# Sheet1.net
KiCad netlist of a schematic drawn in Altium Designer
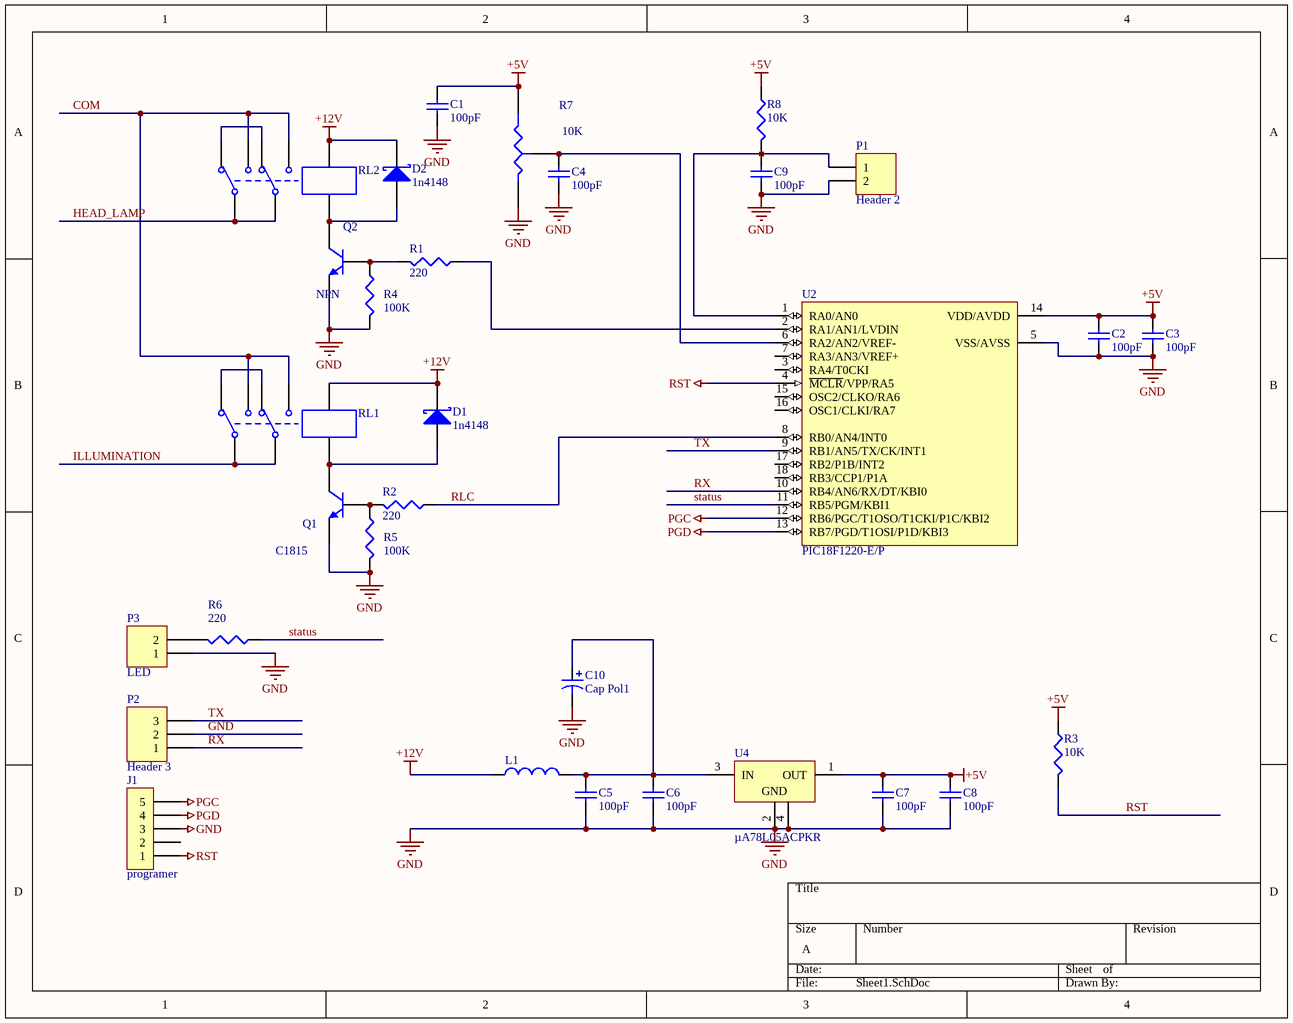
[diagram p0: Sheet1.SchDoc]

(export (version "E")
  (design (tool "Eeschema 10.0.6"))
  (components
    (comp (ref "C1")
      (value "100pF")
      (footprint "RESC2012L")
      (description "Capacitor (Semiconductor SIM Model)")
      (fields (field (name "Comment") "Cap Semi") (field (name "PUBLISHER") "Altium Limited"))
      (libsource (lib "Miscellaneous Devices") (part "Cap Semi"))
    )
    (comp (ref "C2")
      (value "100pF")
      (footprint "RESC2012L")
      (description "Capacitor (Semiconductor SIM Model)")
      (fields (field (name "Comment") "Cap Semi") (field (name "PUBLISHER") "Altium Limited"))
      (libsource (lib "Miscellaneous Devices") (part "Cap Semi"))
    )
    (comp (ref "C3")
      (value "100pF")
      (footprint "RESC2012L")
      (description "Capacitor (Semiconductor SIM Model)")
      (fields (field (name "Comment") "Cap Semi") (field (name "PUBLISHER") "Altium Limited"))
      (libsource (lib "Miscellaneous Devices") (part "Cap Semi"))
    )
    (comp (ref "C4")
      (value "100pF")
      (footprint "RESC2012L")
      (description "Capacitor (Semiconductor SIM Model)")
      (fields (field (name "Comment") "Cap Semi") (field (name "PUBLISHER") "Altium Limited"))
      (libsource (lib "Miscellaneous Devices") (part "Cap Semi"))
    )
    (comp (ref "C5")
      (value "100pF")
      (footprint "RESC2012L")
      (description "Capacitor (Semiconductor SIM Model)")
      (fields (field (name "Comment") "Cap Semi") (field (name "PUBLISHER") "Altium Limited"))
      (libsource (lib "Miscellaneous Devices") (part "Cap Semi"))
    )
    (comp (ref "C6")
      (value "100pF")
      (footprint "RESC2012L")
      (description "Capacitor (Semiconductor SIM Model)")
      (fields (field (name "Comment") "Cap Semi") (field (name "PUBLISHER") "Altium Limited"))
      (libsource (lib "Miscellaneous Devices") (part "Cap Semi"))
    )
    (comp (ref "C7")
      (value "100pF")
      (footprint "RESC2012L")
      (description "Capacitor (Semiconductor SIM Model)")
      (fields (field (name "Comment") "Cap Semi") (field (name "PUBLISHER") "Altium Limited"))
      (libsource (lib "Miscellaneous Devices") (part "Cap Semi"))
    )
    (comp (ref "C8")
      (value "100pF")
      (footprint "RESC2012L")
      (description "Capacitor (Semiconductor SIM Model)")
      (fields (field (name "Comment") "Cap Semi") (field (name "PUBLISHER") "Altium Limited"))
      (libsource (lib "Miscellaneous Devices") (part "Cap Semi"))
    )
    (comp (ref "C9")
      (value "100pF")
      (footprint "RESC2012L")
      (description "Capacitor (Semiconductor SIM Model)")
      (fields (field (name "Comment") "Cap Semi") (field (name "PUBLISHER") "Altium Limited"))
      (libsource (lib "Miscellaneous Devices") (part "Cap Semi"))
    )
    (comp (ref "C10")
      (value "Cap Pol1")
      (footprint "CAP5")
      (description "Polarized Capacitor (Radial)")
      (fields (field (name "PUBLISHER") "Altium Limited"))
      (libsource (lib "Miscellaneous Devices") (part "Cap Pol1"))
    )
    (comp (ref "D1")
      (value "1n4148")
      (footprint "MELF-D5022-2009")
      (description "Schottky Diode")
      (fields (field (name "PUBLISHER") "Altium Limited"))
      (libsource (lib "Schlib1") (part "1N4148_SMD"))
    )
    (comp (ref "D2")
      (value "1n4148")
      (footprint "MELF-D5022-2009")
      (description "Schottky Diode")
      (fields (field (name "PUBLISHER") "Altium Limited"))
      (libsource (lib "Schlib1") (part "1N4148_SMD"))
    )
    (comp (ref "J1")
      (value "programer")
      (footprint "HDR1x5")
      (description "Connector")
      (libsource (lib "*") (part "CON5"))
    )
    (comp (ref "L1")
      (value "~")
      (footprint "INDC3216")
      (description "Inductor")
      (fields (field (name "PUBLISHER") "Altium Limited"))
      (libsource (lib "Miscellaneous Devices") (part "Inductor"))
    )
    (comp (ref "P1")
      (value "Header 2")
      (footprint "HDR1X2")
      (description "Header, 2-Pin")
      (fields (field (name "PUBLISHER") "Altium Limited"))
      (libsource (lib "Miscellaneous Connectors") (part "Header 2"))
    )
    (comp (ref "P2")
      (value "Header 3")
      (footprint "HDR1X3")
      (description "Header, 3-Pin")
      (fields (field (name "PUBLISHER") "Altium Limited"))
      (libsource (lib "Miscellaneous Connectors") (part "Header 3"))
    )
    (comp (ref "P3")
      (value "LED")
      (footprint "HDR1X2")
      (description "Header, 2-Pin")
      (fields (field (name "PUBLISHER") "Altium Limited"))
      (libsource (lib "") (part "Header 2_1"))
    )
    (comp (ref "Q1")
      (value "C1815")
      (footprint "SOT-23B")
      (description "NPN Bipolar Transistor")
      (fields (field (name "PUBLISHER") "Altium Limited"))
      (libsource (lib "Miscellaneous Devices") (part "NPN"))
    )
    (comp (ref "Q2")
      (value "NPN")
      (footprint "SOT-23B")
      (description "NPN Bipolar Transistor")
      (fields (field (name "PUBLISHER") "Altium Limited"))
      (libsource (lib "Miscellaneous Devices") (part "NPN"))
    )
    (comp (ref "R1")
      (value "220")
      (footprint "RESC2012L")
      (description "Resistor")
      (fields (field (name "Comment") "Res3") (field (name "PUBLISHER") "Altium Limited"))
      (libsource (lib "Miscellaneous Devices") (part "Res3"))
    )
    (comp (ref "R2")
      (value "220")
      (footprint "RESC2012L")
      (description "Resistor")
      (fields (field (name "Comment") "Res3") (field (name "PUBLISHER") "Altium Limited"))
      (libsource (lib "Miscellaneous Devices") (part "Res3"))
    )
    (comp (ref "R3")
      (value "10K")
      (footprint "RESC2012L")
      (description "Resistor")
      (fields (field (name "Comment") "Res3") (field (name "PUBLISHER") "Altium Limited"))
      (libsource (lib "Miscellaneous Devices") (part "Res3"))
    )
    (comp (ref "R4")
      (value "100K")
      (footprint "RESC2012L")
      (description "Resistor")
      (fields (field (name "Comment") "Res3") (field (name "PUBLISHER") "Altium Limited"))
      (libsource (lib "Miscellaneous Devices") (part "Res3"))
    )
    (comp (ref "R5")
      (value "100K")
      (footprint "RESC2012L")
      (description "Resistor")
      (fields (field (name "Comment") "Res3") (field (name "PUBLISHER") "Altium Limited"))
      (libsource (lib "Miscellaneous Devices") (part "Res3"))
    )
    (comp (ref "R6")
      (value "220")
      (footprint "RESC2012L")
      (description "Resistor")
      (fields (field (name "Comment") "Res3") (field (name "PUBLISHER") "Altium Limited"))
      (libsource (lib "Miscellaneous Devices") (part "Res3"))
    )
    (comp (ref "R7")
      (value "10K")
      (footprint "VR_V_MH")
      (description "Tapped Resistor")
      (fields (field (name "Comment") "Res Tap") (field (name "PUBLISHER") "Altium Limited"))
      (libsource (lib "Miscellaneous Devices") (part "Res Tap"))
    )
    (comp (ref "R8")
      (value "10K")
      (footprint "RESC2012L")
      (description "Resistor")
      (fields (field (name "Comment") "Res3") (field (name "PUBLISHER") "Altium Limited"))
      (libsource (lib "Miscellaneous Devices") (part "Res3"))
    )
    (comp (ref "RL1")
      (value "Relay-DPDT")
      (footprint "RELAY_8PIN_MH")
      (description "Dual-Pole Dual-Throw Relay")
      (fields (field (name "PUBLISHER") "Altium Limited"))
      (libsource (lib "Miscellaneous Devices") (part "Relay-DPDT"))
    )
    (comp (ref "RL2")
      (value "Relay-DPDT")
      (footprint "RELAY_8PIN_MH")
      (description "Dual-Pole Dual-Throw Relay")
      (fields (field (name "PUBLISHER") "Altium Limited"))
      (libsource (lib "Miscellaneous Devices") (part "Relay-DPDT"))
    )
    (comp (ref "U2")
      (value "PIC18F1220-E/P")
      (footprint "PDIP300-P18")
      (fields (field (name "PUBLISHER") "Altium Limited"))
      (libsource (lib "Microchip Microcontroller 8-Bit PIC18") (part "PIC18F1220-E/P"))
    )
    (comp (ref "U4")
      (value "µA78L05ACPKR")
      (footprint "PK03")
      (description "Positive-Voltage Regulator")
      (fields (field (name "PUBLISHER") "Altium Limited"))
      (libsource (lib "Schlib1") (part "µA78L05ACPKR"))
    )
  )
  (nets
    (net (code "1") (name "+5V") (class "Default")
      (node (ref "C1") (pin "2") (pinfunction "2_2") (pintype "passive"))
      (node (ref "C2") (pin "2") (pinfunction "2_2") (pintype "passive"))
      (node (ref "C3") (pin "2") (pinfunction "2_2") (pintype "passive"))
      (node (ref "C7") (pin "2") (pinfunction "2_2") (pintype "passive"))
      (node (ref "C8") (pin "2") (pinfunction "2_2") (pintype "passive"))
      (node (ref "R3") (pin "1") (pinfunction "1_1") (pintype "passive"))
      (node (ref "R7") (pin "2") (pinfunction "B_2") (pintype "passive"))
      (node (ref "R8") (pin "1") (pinfunction "1_1") (pintype "passive"))
      (node (ref "U2") (pin "14") (pinfunction "VDD/AVDD_14") (pintype "power_in"))
      (node (ref "U4") (pin "1") (pinfunction "OUT_1") (pintype "power_in"))
    )
    (net (code "2") (name "+12V") (class "Default")
      (node (ref "D1") (pin "2") (pinfunction "K_2") (pintype "passive"))
      (node (ref "D2") (pin "2") (pinfunction "K_2") (pintype "passive"))
      (node (ref "L1") (pin "1") (pinfunction "1_1") (pintype "passive"))
      (node (ref "RL1") (pin "8") (pinfunction "8_8") (pintype "passive"))
      (node (ref "RL2") (pin "8") (pinfunction "8_8") (pintype "passive"))
    )
    (net (code "3") (name "/COM") (class "Default")
      (node (ref "RL1") (pin "3") (pinfunction "3_3") (pintype "passive"))
      (node (ref "RL1") (pin "6") (pinfunction "6_6") (pintype "passive"))
      (node (ref "RL2") (pin "3") (pinfunction "3_3") (pintype "passive"))
      (node (ref "RL2") (pin "6") (pinfunction "6_6") (pintype "passive"))
    )
    (net (code "4") (name "/HEAD_LAMP") (class "Default")
      (node (ref "RL2") (pin "1") (pinfunction "1_1") (pintype "passive"))
      (node (ref "RL2") (pin "4") (pinfunction "4_4") (pintype "passive"))
    )
    (net (code "5") (name "/ILLUMINATION") (class "Default")
      (node (ref "RL1") (pin "1") (pinfunction "1_1") (pintype "passive"))
      (node (ref "RL1") (pin "4") (pinfunction "4_4") (pintype "passive"))
    )
    (net (code "6") (name "/RLC") (class "Default")
      (node (ref "R2") (pin "1") (pinfunction "1_1") (pintype "passive"))
      (node (ref "U2") (pin "8") (pinfunction "RB0/AN4/INT0_8") (pintype "bidirectional"))
    )
    (net (code "7") (name "/RX") (class "Default")
      (node (ref "P2") (pin "1") (pinfunction "1_1") (pintype "passive"))
      (node (ref "U2") (pin "10") (pinfunction "RB4/AN6/RX/DT/KBI0_10") (pintype "bidirectional"))
    )
    (net (code "8") (name "/TX") (class "Default")
      (node (ref "P2") (pin "3") (pinfunction "3_3") (pintype "passive"))
      (node (ref "U2") (pin "9") (pinfunction "RB1/AN5/TX/CK/INT1_9") (pintype "bidirectional"))
    )
    (net (code "9") (name "/status") (class "Default")
      (node (ref "R6") (pin "1") (pinfunction "1_1") (pintype "passive"))
      (node (ref "U2") (pin "11") (pinfunction "RB5/PGM/KBI1_11") (pintype "bidirectional"))
    )
    (net (code "10") (name "GND") (class "Default")
      (node (ref "C1") (pin "1") (pinfunction "1_1") (pintype "passive"))
      (node (ref "C10") (pin "2") (pinfunction "2_2") (pintype "passive"))
      (node (ref "C2") (pin "1") (pinfunction "1_1") (pintype "passive"))
      (node (ref "C3") (pin "1") (pinfunction "1_1") (pintype "passive"))
      (node (ref "C4") (pin "1") (pinfunction "1_1") (pintype "passive"))
      (node (ref "C5") (pin "1") (pinfunction "1_1") (pintype "passive"))
      (node (ref "C6") (pin "1") (pinfunction "1_1") (pintype "passive"))
      (node (ref "C7") (pin "1") (pinfunction "1_1") (pintype "passive"))
      (node (ref "C8") (pin "1") (pinfunction "1_1") (pintype "passive"))
      (node (ref "C9") (pin "1") (pinfunction "1_1") (pintype "passive"))
      (node (ref "J1") (pin "3") (pinfunction "3_3") (pintype "passive"))
      (node (ref "P1") (pin "2") (pinfunction "2_2") (pintype "passive"))
      (node (ref "P2") (pin "2") (pinfunction "2_2") (pintype "passive"))
      (node (ref "P3") (pin "1") (pinfunction "1_1") (pintype "passive"))
      (node (ref "Q1") (pin "3") (pinfunction "E_3") (pintype "passive"))
      (node (ref "Q2") (pin "3") (pinfunction "E_3") (pintype "passive"))
      (node (ref "R4") (pin "2") (pinfunction "2_2") (pintype "passive"))
      (node (ref "R5") (pin "2") (pinfunction "2_2") (pintype "passive"))
      (node (ref "R7") (pin "1") (pinfunction "A_1") (pintype "passive"))
      (node (ref "U2") (pin "5") (pinfunction "VSS/AVSS_5") (pintype "power_in"))
      (node (ref "U4") (pin "2") (pinfunction "GND_2") (pintype "power_in"))
      (node (ref "U4") (pin "4") (pinfunction "GND_4") (pintype "power_in"))
    )
    (net (code "11") (name "Net-(D1-A)") (class "Default")
      (node (ref "D1") (pin "1") (pinfunction "A_1") (pintype "passive"))
      (node (ref "Q1") (pin "1") (pinfunction "C_1") (pintype "passive"))
      (node (ref "RL1") (pin "7") (pinfunction "7_7") (pintype "passive"))
    )
    (net (code "12") (name "Net-(D2-A)") (class "Default")
      (node (ref "D2") (pin "1") (pinfunction "A_1") (pintype "passive"))
      (node (ref "Q2") (pin "1") (pinfunction "C_1") (pintype "passive"))
      (node (ref "RL2") (pin "7") (pinfunction "7_7") (pintype "passive"))
    )
    (net (code "13") (name "Net-(P3-Pad2)") (class "Default")
      (node (ref "P3") (pin "2") (pinfunction "2_2") (pintype "passive"))
      (node (ref "R6") (pin "2") (pinfunction "2_2") (pintype "passive"))
    )
    (net (code "14") (name "Net-(Q1-B)") (class "Default")
      (node (ref "Q1") (pin "2") (pinfunction "B_2") (pintype "passive"))
      (node (ref "R2") (pin "2") (pinfunction "2_2") (pintype "passive"))
      (node (ref "R5") (pin "1") (pinfunction "1_1") (pintype "passive"))
    )
    (net (code "15") (name "Net-(Q2-B)") (class "Default")
      (node (ref "Q2") (pin "2") (pinfunction "B_2") (pintype "passive"))
      (node (ref "R1") (pin "2") (pinfunction "2_2") (pintype "passive"))
      (node (ref "R4") (pin "1") (pinfunction "1_1") (pintype "passive"))
    )
    (net (code "16") (name "Net-(R7-TAP)") (class "Default")
      (node (ref "C4") (pin "2") (pinfunction "2_2") (pintype "passive"))
      (node (ref "R7") (pin "3") (pinfunction "TAP_3") (pintype "passive"))
      (node (ref "U2") (pin "6") (pinfunction "RA2/AN2/VREF-_6") (pintype "bidirectional"))
    )
    (net (code "17") (name "Net-(RL1-Pad2)") (class "Default")
      (node (ref "RL1") (pin "2") (pinfunction "2_2") (pintype "passive"))
      (node (ref "RL1") (pin "5") (pinfunction "5_5") (pintype "passive"))
    )
    (net (code "18") (name "Net-(RL2-Pad2)") (class "Default")
      (node (ref "RL2") (pin "2") (pinfunction "2_2") (pintype "passive"))
      (node (ref "RL2") (pin "5") (pinfunction "5_5") (pintype "passive"))
    )
    (net (code "19") (name "Net-(U2-RA0{slash}AN0)") (class "Default")
      (node (ref "C9") (pin "2") (pinfunction "2_2") (pintype "passive"))
      (node (ref "P1") (pin "1") (pinfunction "1_1") (pintype "passive"))
      (node (ref "R8") (pin "2") (pinfunction "2_2") (pintype "passive"))
      (node (ref "U2") (pin "1") (pinfunction "RA0/AN0_1") (pintype "bidirectional"))
    )
    (net (code "20") (name "Net-(U2-RA1{slash}AN1{slash}LVDIN)") (class "Default")
      (node (ref "R1") (pin "1") (pinfunction "1_1") (pintype "passive"))
      (node (ref "U2") (pin "2") (pinfunction "RA1/AN1/LVDIN_2") (pintype "bidirectional"))
    )
    (net (code "21") (name "Net-(U4-IN)") (class "Default")
      (node (ref "C10") (pin "1") (pinfunction "1_1") (pintype "passive"))
      (node (ref "C5") (pin "2") (pinfunction "2_2") (pintype "passive"))
      (node (ref "C6") (pin "2") (pinfunction "2_2") (pintype "passive"))
      (node (ref "L1") (pin "2") (pinfunction "2_2") (pintype "passive"))
      (node (ref "U4") (pin "3") (pinfunction "IN_3") (pintype "power_in"))
    )
    (net (code "22") (name "PGC") (class "Default")
      (node (ref "J1") (pin "5") (pinfunction "5_5") (pintype "passive"))
      (node (ref "U2") (pin "12") (pinfunction "RB6/PGC/T1OSO/T1CKI/P1C/KBI2_12") (pintype "bidirectional"))
    )
    (net (code "23") (name "PGD") (class "Default")
      (node (ref "J1") (pin "4") (pinfunction "4_4") (pintype "passive"))
      (node (ref "U2") (pin "13") (pinfunction "RB7/PGD/T1OSI/P1D/KBI3_13") (pintype "bidirectional"))
    )
    (net (code "24") (name "RST") (class "Default")
      (node (ref "J1") (pin "1") (pinfunction "1_1") (pintype "passive"))
      (node (ref "R3") (pin "2") (pinfunction "2_2") (pintype "passive"))
      (node (ref "U2") (pin "4") (pinfunction "~{MCLR}/VPP/RA5_4") (pintype "input"))
    )
    (net (code "25") (name "unconnected-(J1-Pad2)") (class "Default")
      (node (ref "J1") (pin "2") (pinfunction "2_2") (pintype "passive"))
    )
    (net (code "26") (name "unconnected-(U2-OSC1{slash}CLKI{slash}RA7-Pad16)") (class "Default")
      (node (ref "U2") (pin "16") (pinfunction "OSC1/CLKI/RA7_16") (pintype "bidirectional"))
    )
    (net (code "27") (name "unconnected-(U2-OSC2{slash}CLKO{slash}RA6-Pad15)") (class "Default")
      (node (ref "U2") (pin "15") (pinfunction "OSC2/CLKO/RA6_15") (pintype "bidirectional"))
    )
    (net (code "28") (name "unconnected-(U2-RA3{slash}AN3{slash}VREF+-Pad7)") (class "Default")
      (node (ref "U2") (pin "7") (pinfunction "RA3/AN3/VREF+_7") (pintype "bidirectional"))
    )
    (net (code "29") (name "unconnected-(U2-RA4{slash}T0CKI-Pad3)") (class "Default")
      (node (ref "U2") (pin "3") (pinfunction "RA4/T0CKI_3") (pintype "bidirectional"))
    )
    (net (code "30") (name "unconnected-(U2-RB2{slash}P1B{slash}INT2-Pad17)") (class "Default")
      (node (ref "U2") (pin "17") (pinfunction "RB2/P1B/INT2_17") (pintype "bidirectional"))
    )
    (net (code "31") (name "unconnected-(U2-RB3{slash}CCP1{slash}P1A-Pad18)") (class "Default")
      (node (ref "U2") (pin "18") (pinfunction "RB3/CCP1/P1A_18") (pintype "bidirectional"))
    )
  )
)
